# reciever_board.net
KiCad netlist of a schematic drawn in EAGLE
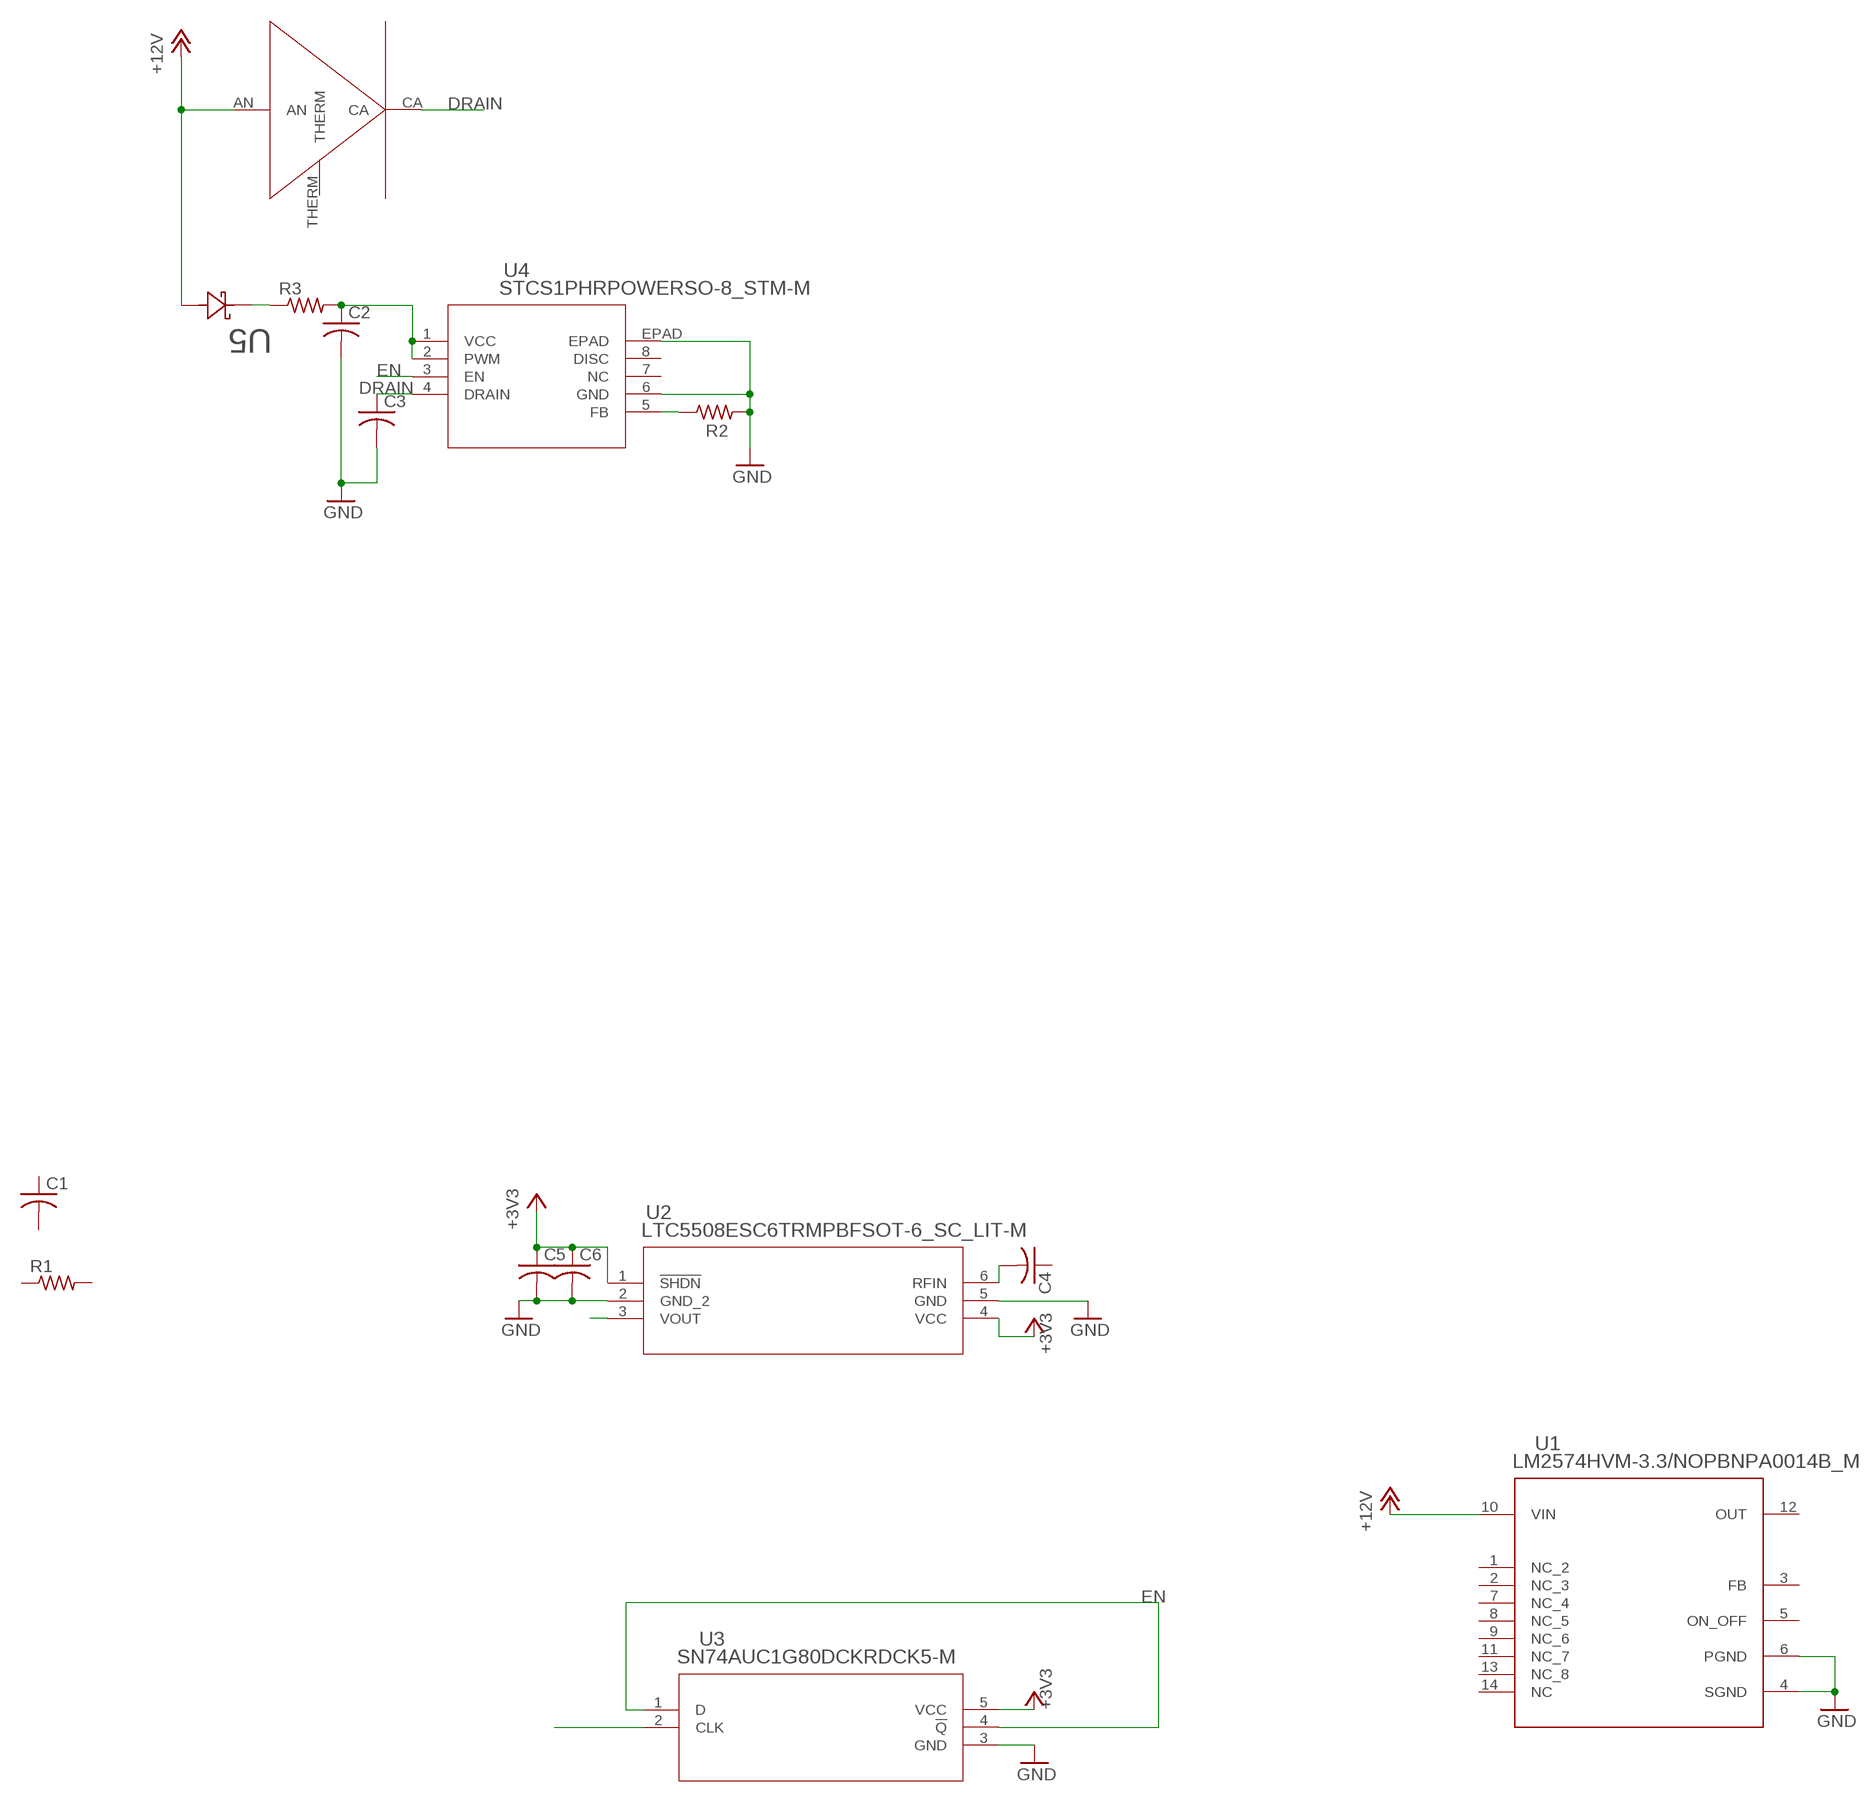
[diagram p0: schematic, sheet 1]

(export (version "E")
  (design (tool "Eeschema 10.0.6"))
  (components
    (comp (ref "C1")
      (value "C-USC0603")
      (footprint "eagle-import:C0603")
      (libsource (lib "eagle-import") (part "C-USC0603"))
    )
    (comp (ref "C2")
      (value "C-USC0603")
      (footprint "eagle-import:C0603")
      (libsource (lib "eagle-import") (part "C-USC0603"))
    )
    (comp (ref "C3")
      (value "C-USC0603")
      (footprint "eagle-import:C0603")
      (libsource (lib "eagle-import") (part "C-USC0603"))
    )
    (comp (ref "C4")
      (value "C-USC0603")
      (footprint "eagle-import:C0603")
      (libsource (lib "eagle-import") (part "C-USC0603"))
    )
    (comp (ref "C5")
      (value "C-USC0603")
      (footprint "eagle-import:C0603")
      (libsource (lib "eagle-import") (part "C-USC0603"))
    )
    (comp (ref "C6")
      (value "C-USC0603")
      (footprint "eagle-import:C0603")
      (libsource (lib "eagle-import") (part "C-USC0603"))
    )
    (comp (ref "R1")
      (value "R-US_R0603")
      (footprint "eagle-import:R0603")
      (libsource (lib "eagle-import") (part "R-US_R0603"))
    )
    (comp (ref "R2")
      (value "R-US_R0603")
      (footprint "eagle-import:R0603")
      (libsource (lib "eagle-import") (part "R-US_R0603"))
    )
    (comp (ref "R3")
      (value "R-US_R0603")
      (footprint "eagle-import:R0603")
      (libsource (lib "eagle-import") (part "R-US_R0603"))
    )
    (comp (ref "U$1")
      (value "MKRAWT-02-0000-0D00J2051")
      (footprint "eagle-import:MKRAWT-02-0000-0D00J2051")
      (libsource (lib "eagle-import") (part "MKRAWT-02-0000-0D00J2051"))
    )
    (comp (ref "U1")
      (value "LM2574HVM-3.3/NOPBNPA0014B_M")
      (footprint "eagle-import:NPA0014B_M")
      (fields
        (field (name "MANUFACTURER_PART_NUMBER") "LM2574HVM-3.3/NOPB")
        (field (name "COPYRIGHT") "Copyright (C) 2022 Ultra Librarian. All rights reserved.")
      )
      (libsource (lib "eagle-import") (part "LM2574HVM-3.3/NOPBNPA0014B_M"))
    )
    (comp (ref "U2")
      (value "LTC5508ESC6TRMPBFSOT-6_SC_LIT-M")
      (footprint "eagle-import:SOT-6_SC_LIT-M")
      (fields
        (field (name "MANUFACTURER_PART_NUMBER") "LTC5508ESC6#TRMPBF")
        (field (name "COPYRIGHT") "Copyright (C) 2022 Ultra Librarian. All rights reserved.")
      )
      (libsource (lib "eagle-import") (part "LTC5508ESC6TRMPBFSOT-6_SC_LIT-M"))
    )
    (comp (ref "U3")
      (value "SN74AUC1G80DCKRDCK5-M")
      (footprint "eagle-import:DCK5-M")
      (fields
        (field (name "MANUFACTURER_PART_NUMBER") "SN74AUC1G80DCKR")
        (field (name "COPYRIGHT") "Copyright (C) 2022 Ultra Librarian. All rights reserved.")
      )
      (libsource (lib "eagle-import") (part "SN74AUC1G80DCKRDCK5-M"))
    )
    (comp (ref "U4")
      (value "STCS1PHRPOWERSO-8_STM-M")
      (footprint "eagle-import:POWERSO-8_STM-M")
      (fields
        (field (name "MANUFACTURER_PART_NUMBER") "STCS1PHR")
        (field (name "COPYRIGHT") "Copyright (C) 2022 Ultra Librarian. All rights reserved.")
      )
      (libsource (lib "eagle-import") (part "STCS1PHRPOWERSO-8_STM-M"))
    )
    (comp (ref "U5")
      (value "CDBW46-GCDBW-M")
      (footprint "eagle-import:CDBW-M")
      (fields
        (field (name "MANUFACTURER_PART_NUMBER") "CDBW46-G")
        (field (name "COPYRIGHT") "Copyright (C) 2022 Ultra Librarian. All rights reserved.")
      )
      (libsource (lib "eagle-import") (part "CDBW46-GCDBW-M"))
    )
  )
  (nets
    (net (code "1") (name "+3V3") (class "Default")
      (node (ref "C5") (pin "1") (pinfunction "1_1") (pintype "passive"))
      (node (ref "C6") (pin "1") (pinfunction "1_1") (pintype "passive"))
      (node (ref "U2") (pin "1") (pinfunction "~{SHDN}_1") (pintype "passive"))
      (node (ref "U2") (pin "4") (pinfunction "VCC_4") (pintype "power_in"))
      (node (ref "U3") (pin "5") (pinfunction "VCC_5") (pintype "power_in"))
    )
    (net (code "2") (name "+12V") (class "Default")
      (node (ref "U$1") (pin "AN") (pinfunction "AN_AN") (pintype "passive"))
      (node (ref "U1") (pin "10") (pinfunction "VIN_10") (pintype "power_in"))
      (node (ref "U5") (pin "2") (pinfunction "2_2") (pintype "passive"))
    )
    (net (code "3") (name "/DRAIN") (class "Default")
      (node (ref "C3") (pin "1") (pinfunction "1_1") (pintype "passive"))
      (node (ref "U$1") (pin "CA") (pinfunction "CA_CA") (pintype "passive"))
      (node (ref "U4") (pin "4") (pinfunction "DRAIN_4") (pintype "output"))
    )
    (net (code "4") (name "/EN") (class "Default")
      (node (ref "U3") (pin "1") (pinfunction "D_1") (pintype "input"))
      (node (ref "U3") (pin "4") (pinfunction "~{Q}_4") (pintype "output"))
      (node (ref "U4") (pin "3") (pinfunction "EN_3") (pintype "input"))
    )
    (net (code "5") (name "/OUT") (class "Default")
      (node (ref "U1") (pin "12") (pinfunction "OUT_12") (pintype "power_in"))
    )
    (net (code "6") (name "GND") (class "Default")
      (node (ref "C2") (pin "2") (pinfunction "2_2") (pintype "passive"))
      (node (ref "C3") (pin "2") (pinfunction "2_2") (pintype "passive"))
      (node (ref "C5") (pin "2") (pinfunction "2_2") (pintype "passive"))
      (node (ref "C6") (pin "2") (pinfunction "2_2") (pintype "passive"))
      (node (ref "R2") (pin "2") (pinfunction "2_2") (pintype "passive"))
      (node (ref "U1") (pin "4") (pinfunction "SGND_4") (pintype "power_in"))
      (node (ref "U1") (pin "6") (pinfunction "PGND_6") (pintype "power_in"))
      (node (ref "U2") (pin "2") (pinfunction "GND_2_2") (pintype "power_in"))
      (node (ref "U2") (pin "5") (pinfunction "GND_5") (pintype "power_in"))
      (node (ref "U3") (pin "3") (pinfunction "GND_3") (pintype "power_in"))
      (node (ref "U4") (pin "6") (pinfunction "GND_6") (pintype "passive"))
      (node (ref "U4") (pin "EPAD") (pinfunction "EPAD_EPAD") (pintype "passive"))
    )
    (net (code "7") (name "Net-(R3-Pad1)") (class "Default")
      (node (ref "R3") (pin "1") (pinfunction "1_1") (pintype "passive"))
      (node (ref "U5") (pin "1") (pinfunction "1_1") (pintype "passive"))
    )
    (net (code "8") (name "Net-(U2-RFIN)") (class "Default")
      (node (ref "C4") (pin "2") (pinfunction "2_2") (pintype "passive"))
      (node (ref "U2") (pin "6") (pinfunction "RFIN_6") (pintype "input"))
    )
    (net (code "9") (name "Net-(U4-FB)") (class "Default")
      (node (ref "R2") (pin "1") (pinfunction "1_1") (pintype "passive"))
      (node (ref "U4") (pin "5") (pinfunction "FB_5") (pintype "input"))
    )
    (net (code "10") (name "Net-(U4-PWM)") (class "Default")
      (node (ref "C2") (pin "1") (pinfunction "1_1") (pintype "passive"))
      (node (ref "R3") (pin "2") (pinfunction "2_2") (pintype "passive"))
      (node (ref "U4") (pin "1") (pinfunction "VCC_1") (pintype "power_in"))
      (node (ref "U4") (pin "2") (pinfunction "PWM_2") (pintype "input"))
    )
    (net (code "11") (name "unconnected-(C1-Pad1)") (class "Default")
      (node (ref "C1") (pin "1") (pinfunction "1_1") (pintype "passive"))
    )
    (net (code "12") (name "unconnected-(C1-Pad2)") (class "Default")
      (node (ref "C1") (pin "2") (pinfunction "2_2") (pintype "passive"))
    )
    (net (code "13") (name "unconnected-(C4-Pad1)") (class "Default")
      (node (ref "C4") (pin "1") (pinfunction "1_1") (pintype "passive"))
    )
    (net (code "14") (name "unconnected-(R1-Pad1)") (class "Default")
      (node (ref "R1") (pin "1") (pinfunction "1_1") (pintype "passive"))
    )
    (net (code "15") (name "unconnected-(R1-Pad2)") (class "Default")
      (node (ref "R1") (pin "2") (pinfunction "2_2") (pintype "passive"))
    )
    (net (code "16") (name "unconnected-(U$1-PadTHERM)") (class "Default")
      (node (ref "U$1") (pin "THERM") (pinfunction "THERM_THERM") (pintype "passive"))
    )
    (net (code "17") (name "unconnected-(U1-FB-Pad3)") (class "Default")
      (node (ref "U1") (pin "3") (pinfunction "FB_3") (pintype "input"))
    )
    (net (code "18") (name "unconnected-(U1-NC-Pad14)") (class "Default")
      (node (ref "U1") (pin "14") (pinfunction "NC_14") (pintype "passive"))
    )
    (net (code "19") (name "unconnected-(U1-NC_2-Pad1)") (class "Default")
      (node (ref "U1") (pin "1") (pinfunction "NC_2_1") (pintype "passive"))
    )
    (net (code "20") (name "unconnected-(U1-NC_3-Pad2)") (class "Default")
      (node (ref "U1") (pin "2") (pinfunction "NC_3_2") (pintype "passive"))
    )
    (net (code "21") (name "unconnected-(U1-NC_4-Pad7)") (class "Default")
      (node (ref "U1") (pin "7") (pinfunction "NC_4_7") (pintype "passive"))
    )
    (net (code "22") (name "unconnected-(U1-NC_5-Pad8)") (class "Default")
      (node (ref "U1") (pin "8") (pinfunction "NC_5_8") (pintype "passive"))
    )
    (net (code "23") (name "unconnected-(U1-NC_6-Pad9)") (class "Default")
      (node (ref "U1") (pin "9") (pinfunction "NC_6_9") (pintype "passive"))
    )
    (net (code "24") (name "unconnected-(U1-NC_7-Pad11)") (class "Default")
      (node (ref "U1") (pin "11") (pinfunction "NC_7_11") (pintype "passive"))
    )
    (net (code "25") (name "unconnected-(U1-NC_8-Pad13)") (class "Default")
      (node (ref "U1") (pin "13") (pinfunction "NC_8_13") (pintype "passive"))
    )
    (net (code "26") (name "unconnected-(U1-ON_OFF-Pad5)") (class "Default")
      (node (ref "U1") (pin "5") (pinfunction "ON_OFF_5") (pintype "input"))
    )
    (net (code "27") (name "unconnected-(U2-VOUT-Pad3)") (class "Default")
      (node (ref "U2") (pin "3") (pinfunction "VOUT_3") (pintype "output"))
    )
    (net (code "28") (name "unconnected-(U3-CLK-Pad2)") (class "Default")
      (node (ref "U3") (pin "2") (pinfunction "CLK_2") (pintype "input"))
    )
    (net (code "29") (name "unconnected-(U4-DISC-Pad8)") (class "Default")
      (node (ref "U4") (pin "8") (pinfunction "DISC_8") (pintype "output"))
    )
    (net (code "30") (name "unconnected-(U4-NC-Pad7)") (class "Default")
      (node (ref "U4") (pin "7") (pinfunction "NC_7") (pintype "no_connect"))
    )
  )
)
